# BLE_Monitor_Orientation_Sensor.net
KiCad netlist of a schematic drawn in EAGLE
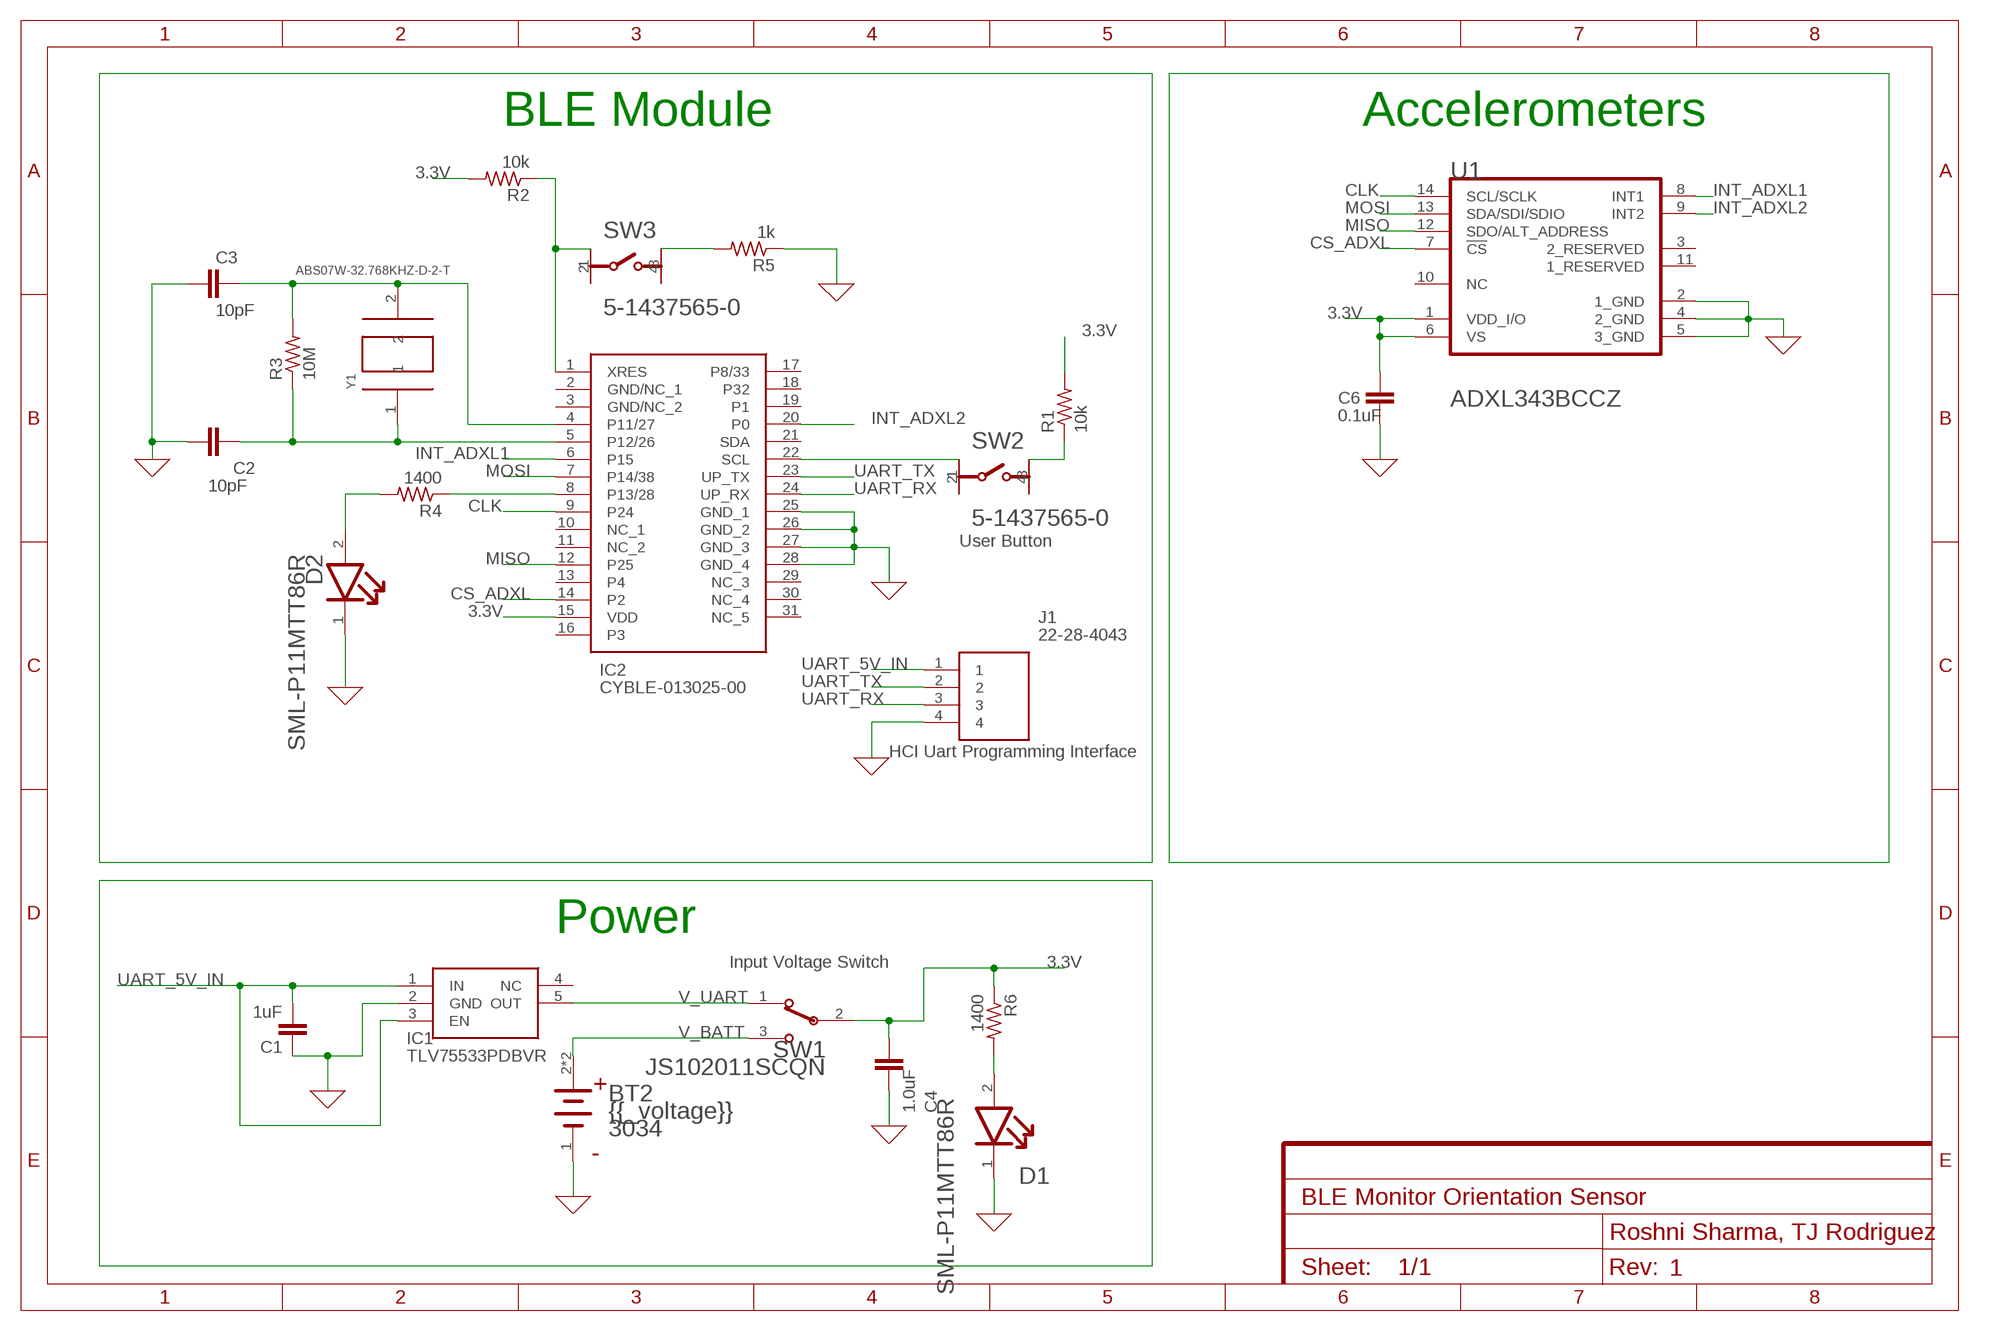
[diagram p0: schematic, sheet 1]

(export (version "E")
  (design (tool "Eeschema 10.0.6"))
  (components
    (comp (ref "BT2")
      (value "KEYSTONE_ELECTRONICS_3034KEYSTONE_ELECTRONICS_3034_0_0")
      (footprint "eagle-import:KEYSTONE_ELECTRONICS_3034_0")
      (fields
        (field (name "DIGIKEY_PART_NUMBER") "36-3034-ND")
        (field (name "MF") "Keystone Electronics")
        (field (name "MOUSER_PART_NUMBER") "534-3034")
      )
      (libsource (lib "eagle-import") (part "KEYSTONE_ELECTRONICS_3034KEYSTONE_ELECTRONICS_3034_0_0"))
    )
    (comp (ref "C1")
      (value "1uF")
      (footprint "eagle-import:0603")
      (libsource (lib "eagle-import") (part "10PF-0603-50V-5%"))
    )
    (comp (ref "C2")
      (value "10pF")
      (footprint "eagle-import:0603")
      (libsource (lib "eagle-import") (part "10PF-0603-50V-5%"))
    )
    (comp (ref "C3")
      (value "10pF")
      (footprint "eagle-import:0603")
      (libsource (lib "eagle-import") (part "10PF-0603-50V-5%"))
    )
    (comp (ref "C4")
      (value "1.0uF")
      (footprint "eagle-import:0603")
      (libsource (lib "eagle-import") (part "1.0UF-0603-16V-10%"))
    )
    (comp (ref "C6")
      (value "0.1uF")
      (footprint "eagle-import:0603")
      (libsource (lib "eagle-import") (part "10PF-0603-50V-5%"))
    )
    (comp (ref "D1")
      (value "ROHM_SML-P11MTT86RROHM_SML-P11MTT86R_0_0")
      (footprint "eagle-import:ROHM_SML-P11MTT86R_0")
      (fields
        (field (name "DIGIKEY_PART_NUMBER") "846-1211-1-ND")
        (field (name "MF") "ROHM")
        (field (name "MOUSER_PART_NUMBER") "755-SML-P11MTT86R")
      )
      (libsource (lib "eagle-import") (part "ROHM_SML-P11MTT86RROHM_SML-P11MTT86R_0_0"))
    )
    (comp (ref "D2")
      (value "ROHM_SML-P11MTT86RROHM_SML-P11MTT86R_0_0")
      (footprint "eagle-import:ROHM_SML-P11MTT86R_0")
      (fields
        (field (name "DIGIKEY_PART_NUMBER") "846-1211-1-ND")
        (field (name "MF") "ROHM")
        (field (name "MOUSER_PART_NUMBER") "755-SML-P11MTT86R")
      )
      (libsource (lib "eagle-import") (part "ROHM_SML-P11MTT86RROHM_SML-P11MTT86R_0_0"))
    )
    (comp (ref "IC1")
      (value "TLV75533PDBVR")
      (footprint "eagle-import:SOT95P280X145-5N")
      (fields (field (name "MOUSER_PART_NUMBER") "595-TLV75533PDBVR"))
      (libsource (lib "eagle-import") (part "TLV75533PDBVR"))
    )
    (comp (ref "IC2")
      (value "CYBLE-013025-00")
      (footprint "eagle-import:CYBLE01302500")
      (fields (field (name "MOUSER_PART_NUMBER") "727-CYBLE-013025-00") (field (name "SPICEPREFIX") "X"))
      (libsource (lib "eagle-import") (part "CYBLE-013025-00"))
    )
    (comp (ref "J1")
      (value "22-28-4043")
      (footprint "eagle-import:HDRV4W87P0X254_1X4_1016X249X86")
      (fields
        (field (name "MOUSER_PART_NUMBER") "538-22-28-4043")
        (field (name "FUNCTION") "HCI Uart Programming Interface")
      )
      (libsource (lib "eagle-import") (part "22-28-4043"))
    )
    (comp (ref "R1")
      (value "10k")
      (footprint "eagle-import:R0603")
      (libsource (lib "eagle-import") (part "R-US_R0603"))
    )
    (comp (ref "R2")
      (value "10k")
      (footprint "eagle-import:R0603")
      (libsource (lib "eagle-import") (part "R-US_R0603"))
    )
    (comp (ref "R3")
      (value "10M")
      (footprint "eagle-import:R0603")
      (libsource (lib "eagle-import") (part "R-US_R0603"))
    )
    (comp (ref "R4")
      (value "1400")
      (footprint "eagle-import:R0603")
      (libsource (lib "eagle-import") (part "R-US_R0603"))
    )
    (comp (ref "R5")
      (value "1k")
      (footprint "eagle-import:R0603")
      (libsource (lib "eagle-import") (part "R-US_R0603"))
    )
    (comp (ref "R6")
      (value "1400")
      (footprint "eagle-import:R0603")
      (libsource (lib "eagle-import") (part "R-US_R0603"))
    )
    (comp (ref "SW1")
      (value "C&K_JS102011SCQNC&K_JS102011SCQN_0_0")
      (footprint "eagle-import:C&K_JS102011SCQN_0")
      (fields
        (field (name "DIGIKEY_PART_NUMBER") "CKN10877CT-ND")
        (field (name "MF") "C&K")
        (field (name "MOUSER_PART_NUMBER") "611-JS102011SCQN")
        (field (name "FUNCTION") "Input Voltage Switch")
      )
      (libsource (lib "eagle-import") (part "C&K_JS102011SCQNC&K_JS102011SCQN_0_0"))
    )
    (comp (ref "SW2")
      (value "TE_CONNECTIVITY_5-1437565-0TE_CONNECTIVITY_5-1437565-0_0_0")
      (footprint "eagle-import:TE_CONNECTIVITY_5-1437565-0_0")
      (fields
        (field (name "DIGIKEY_PART_NUMBER") "450-2058-1-ND")
        (field (name "MF") "TE Connectivity")
        (field (name "MOUSER_PART_NUMBER") "506-5-1437565-0")
        (field (name "FUNCTION") "User Button")
      )
      (libsource (lib "eagle-import") (part "TE_CONNECTIVITY_5-1437565-0TE_CONNECTIVITY_5-1437565-0_0_0"))
    )
    (comp (ref "SW3")
      (value "TE_CONNECTIVITY_5-1437565-0TE_CONNECTIVITY_5-1437565-0_0_0")
      (footprint "eagle-import:TE_CONNECTIVITY_5-1437565-0_0")
      (fields
        (field (name "DIGIKEY_PART_NUMBER") "450-2058-1-ND")
        (field (name "MF") "TE Connectivity")
        (field (name "MOUSER_PART_NUMBER") "506-5-1437565-0")
      )
      (libsource (lib "eagle-import") (part "TE_CONNECTIVITY_5-1437565-0TE_CONNECTIVITY_5-1437565-0_0_0"))
    )
    (comp (ref "U1")
      (value "ANALOG_DEVICES_ADXL343BCCZANALOG_DEVICES_ADXL343BCCZ_0_0")
      (footprint "eagle-import:ANALOG_DEVICES_ADXL343BCCZ_0")
      (fields (field (name "MF") "Analog Devices") (field (name "MPN") "ADXL343BCCZ"))
      (libsource (lib "eagle-import") (part "ANALOG_DEVICES_ADXL343BCCZANALOG_DEVICES_ADXL343BCCZ_0_0"))
    )
    (comp (ref "Y1")
      (value "ABS07W-32.768KHZ-D-2-T")
      (footprint "eagle-import:XTAL320X150X90")
      (fields
        (field (name "DIGI-KEY_PART_NUMBER") "535-14105-1-ND")
        (field (name "MF") "Abracon")
        (field (name "SPICEPREFIX") "B")
      )
      (libsource (lib "eagle-import") (part "ABS07W-32.768KHZ-D-2-T"))
    )
  )
  (nets
    (net (code "1") (name "/3.3V") (class "Default")
      (node (ref "C4") (pin "1") (pinfunction "1_1") (pintype "passive"))
      (node (ref "C6") (pin "2") (pinfunction "2_2") (pintype "passive"))
      (node (ref "IC2") (pin "15") (pinfunction "VDD_15") (pintype "bidirectional"))
      (node (ref "R1") (pin "2") (pinfunction "2_2") (pintype "passive"))
      (node (ref "R2") (pin "2") (pinfunction "2_2") (pintype "passive"))
      (node (ref "R6") (pin "1") (pinfunction "1_1") (pintype "passive"))
      (node (ref "SW1") (pin "2") (pinfunction "2_2") (pintype "passive"))
      (node (ref "U1") (pin "1") (pinfunction "VDD_I/O_1") (pintype "power_in"))
      (node (ref "U1") (pin "6") (pinfunction "VS_6") (pintype "power_in"))
    )
    (net (code "2") (name "/CLK") (class "Default")
      (node (ref "IC2") (pin "9") (pinfunction "P24_9") (pintype "bidirectional"))
      (node (ref "U1") (pin "14") (pinfunction "SCL/SCLK_14") (pintype "input"))
    )
    (net (code "3") (name "/CS_ADXL") (class "Default")
      (node (ref "IC2") (pin "14") (pinfunction "P2_14") (pintype "bidirectional"))
      (node (ref "U1") (pin "7") (pinfunction "~{CS}_7") (pintype "input"))
    )
    (net (code "4") (name "/INT_ADXL1") (class "Default")
      (node (ref "IC2") (pin "6") (pinfunction "P15_6") (pintype "bidirectional"))
      (node (ref "U1") (pin "8") (pinfunction "INT1_8") (pintype "output"))
    )
    (net (code "5") (name "/INT_ADXL2") (class "Default")
      (node (ref "IC2") (pin "20") (pinfunction "P0_20") (pintype "bidirectional"))
      (node (ref "U1") (pin "9") (pinfunction "INT2_9") (pintype "output"))
    )
    (net (code "6") (name "/MISO") (class "Default")
      (node (ref "IC2") (pin "12") (pinfunction "P25_12") (pintype "bidirectional"))
      (node (ref "U1") (pin "12") (pinfunction "SDO/ALT_ADDRESS_12") (pintype "bidirectional"))
    )
    (net (code "7") (name "/MOSI") (class "Default")
      (node (ref "IC2") (pin "7") (pinfunction "P14/38_7") (pintype "bidirectional"))
      (node (ref "U1") (pin "13") (pinfunction "SDA/SDI/SDIO_13") (pintype "bidirectional"))
    )
    (net (code "8") (name "/UART_5V_IN") (class "Default")
      (node (ref "C1") (pin "2") (pinfunction "2_2") (pintype "passive"))
      (node (ref "IC1") (pin "1") (pinfunction "IN_1") (pintype "bidirectional"))
      (node (ref "IC1") (pin "3") (pinfunction "EN_3") (pintype "bidirectional"))
      (node (ref "J1") (pin "1") (pinfunction "1_1") (pintype "bidirectional"))
    )
    (net (code "9") (name "/UART_RX") (class "Default")
      (node (ref "IC2") (pin "24") (pinfunction "UP_RX_24") (pintype "bidirectional"))
      (node (ref "J1") (pin "3") (pinfunction "3_3") (pintype "bidirectional"))
    )
    (net (code "10") (name "/UART_TX") (class "Default")
      (node (ref "IC2") (pin "23") (pinfunction "UP_TX_23") (pintype "bidirectional"))
      (node (ref "J1") (pin "2") (pinfunction "2_2") (pintype "bidirectional"))
    )
    (net (code "11") (name "/V_BATT") (class "Default")
      (node (ref "BT2") (pin "2") (pinfunction "ANODE_2") (pintype "passive"))
      (node (ref "BT2") (pin "2-2") (pinfunction "ANODE_2-2") (pintype "passive"))
      (node (ref "SW1") (pin "3") (pinfunction "3_3") (pintype "passive"))
    )
    (net (code "12") (name "/V_UART") (class "Default")
      (node (ref "IC1") (pin "5") (pinfunction "OUT_5") (pintype "bidirectional"))
      (node (ref "SW1") (pin "1") (pinfunction "1_1") (pintype "passive"))
    )
    (net (code "13") (name "GND") (class "Default")
      (node (ref "BT2") (pin "1") (pinfunction "CATHODE_1") (pintype "passive"))
      (node (ref "C1") (pin "1") (pinfunction "1_1") (pintype "passive"))
      (node (ref "C2") (pin "1") (pinfunction "1_1") (pintype "passive"))
      (node (ref "C3") (pin "1") (pinfunction "1_1") (pintype "passive"))
      (node (ref "C4") (pin "2") (pinfunction "2_2") (pintype "passive"))
      (node (ref "C6") (pin "1") (pinfunction "1_1") (pintype "passive"))
      (node (ref "D1") (pin "1") (pinfunction "CATHODE_1") (pintype "passive"))
      (node (ref "D2") (pin "1") (pinfunction "CATHODE_1") (pintype "passive"))
      (node (ref "IC1") (pin "2") (pinfunction "GND_2") (pintype "bidirectional"))
      (node (ref "IC2") (pin "25") (pinfunction "GND_1_25") (pintype "bidirectional"))
      (node (ref "IC2") (pin "26") (pinfunction "GND_2_26") (pintype "bidirectional"))
      (node (ref "IC2") (pin "27") (pinfunction "GND_3_27") (pintype "bidirectional"))
      (node (ref "IC2") (pin "28") (pinfunction "GND_4_28") (pintype "bidirectional"))
      (node (ref "J1") (pin "4") (pinfunction "4_4") (pintype "bidirectional"))
      (node (ref "R5") (pin "1") (pinfunction "1_1") (pintype "passive"))
      (node (ref "U1") (pin "2") (pinfunction "1_GND_2") (pintype "power_in"))
      (node (ref "U1") (pin "4") (pinfunction "2_GND_4") (pintype "power_in"))
      (node (ref "U1") (pin "5") (pinfunction "3_GND_5") (pintype "power_in"))
    )
    (net (code "14") (name "Net-(D1-ANODE)") (class "Default")
      (node (ref "D1") (pin "2") (pinfunction "ANODE_2") (pintype "passive"))
      (node (ref "R6") (pin "2") (pinfunction "2_2") (pintype "passive"))
    )
    (net (code "15") (name "Net-(D2-ANODE)") (class "Default")
      (node (ref "D2") (pin "2") (pinfunction "ANODE_2") (pintype "passive"))
      (node (ref "R4") (pin "2") (pinfunction "2_2") (pintype "passive"))
    )
    (net (code "16") (name "Net-(IC2-P11{slash}27)") (class "Default")
      (node (ref "C3") (pin "2") (pinfunction "2_2") (pintype "passive"))
      (node (ref "IC2") (pin "4") (pinfunction "P11/27_4") (pintype "bidirectional"))
      (node (ref "R3") (pin "2") (pinfunction "2_2") (pintype "passive"))
      (node (ref "Y1") (pin "2") (pinfunction "2_2") (pintype "passive"))
    )
    (net (code "17") (name "Net-(IC2-P12{slash}26)") (class "Default")
      (node (ref "C2") (pin "2") (pinfunction "2_2") (pintype "passive"))
      (node (ref "IC2") (pin "5") (pinfunction "P12/26_5") (pintype "bidirectional"))
      (node (ref "R3") (pin "1") (pinfunction "1_1") (pintype "passive"))
      (node (ref "Y1") (pin "1") (pinfunction "1_1") (pintype "passive"))
    )
    (net (code "18") (name "Net-(IC2-P13{slash}28)") (class "Default")
      (node (ref "IC2") (pin "8") (pinfunction "P13/28_8") (pintype "bidirectional"))
      (node (ref "R4") (pin "1") (pinfunction "1_1") (pintype "passive"))
    )
    (net (code "19") (name "Net-(IC2-SCL)") (class "Default")
      (node (ref "IC2") (pin "22") (pinfunction "SCL_22") (pintype "bidirectional"))
      (node (ref "SW2") (pin "1") (pinfunction "1_1") (pintype "passive"))
    )
    (net (code "20") (name "Net-(IC2-XRES)") (class "Default")
      (node (ref "IC2") (pin "1") (pinfunction "XRES_1") (pintype "bidirectional"))
      (node (ref "R2") (pin "1") (pinfunction "1_1") (pintype "passive"))
      (node (ref "SW3") (pin "1") (pinfunction "1_1") (pintype "passive"))
    )
    (net (code "21") (name "Net-(R1-Pad1)") (class "Default")
      (node (ref "R1") (pin "1") (pinfunction "1_1") (pintype "passive"))
      (node (ref "SW2") (pin "3") (pinfunction "3_3") (pintype "passive"))
    )
    (net (code "22") (name "Net-(R5-Pad2)") (class "Default")
      (node (ref "R5") (pin "2") (pinfunction "2_2") (pintype "passive"))
      (node (ref "SW3") (pin "3") (pinfunction "3_3") (pintype "passive"))
    )
    (net (code "23") (name "unconnected-(IC1-NC-Pad4)") (class "Default")
      (node (ref "IC1") (pin "4") (pinfunction "NC_4") (pintype "no_connect"))
    )
    (net (code "24") (name "unconnected-(IC2-GND{slash}NC_1-Pad2)") (class "Default")
      (node (ref "IC2") (pin "2") (pinfunction "GND/NC_1_2") (pintype "bidirectional"))
    )
    (net (code "25") (name "unconnected-(IC2-GND{slash}NC_2-Pad3)") (class "Default")
      (node (ref "IC2") (pin "3") (pinfunction "GND/NC_2_3") (pintype "bidirectional"))
    )
    (net (code "26") (name "unconnected-(IC2-NC_1-Pad10)") (class "Default")
      (node (ref "IC2") (pin "10") (pinfunction "NC_1_10") (pintype "bidirectional"))
    )
    (net (code "27") (name "unconnected-(IC2-NC_2-Pad11)") (class "Default")
      (node (ref "IC2") (pin "11") (pinfunction "NC_2_11") (pintype "bidirectional"))
    )
    (net (code "28") (name "unconnected-(IC2-NC_3-Pad29)") (class "Default")
      (node (ref "IC2") (pin "29") (pinfunction "NC_3_29") (pintype "bidirectional"))
    )
    (net (code "29") (name "unconnected-(IC2-NC_4-Pad30)") (class "Default")
      (node (ref "IC2") (pin "30") (pinfunction "NC_4_30") (pintype "bidirectional"))
    )
    (net (code "30") (name "unconnected-(IC2-NC_5-Pad31)") (class "Default")
      (node (ref "IC2") (pin "31") (pinfunction "NC_5_31") (pintype "bidirectional"))
    )
    (net (code "31") (name "unconnected-(IC2-P1-Pad19)") (class "Default")
      (node (ref "IC2") (pin "19") (pinfunction "P1_19") (pintype "bidirectional"))
    )
    (net (code "32") (name "unconnected-(IC2-P3-Pad16)") (class "Default")
      (node (ref "IC2") (pin "16") (pinfunction "P3_16") (pintype "bidirectional"))
    )
    (net (code "33") (name "unconnected-(IC2-P4-Pad13)") (class "Default")
      (node (ref "IC2") (pin "13") (pinfunction "P4_13") (pintype "bidirectional"))
    )
    (net (code "34") (name "unconnected-(IC2-P8{slash}33-Pad17)") (class "Default")
      (node (ref "IC2") (pin "17") (pinfunction "P8/33_17") (pintype "bidirectional"))
    )
    (net (code "35") (name "unconnected-(IC2-P32-Pad18)") (class "Default")
      (node (ref "IC2") (pin "18") (pinfunction "P32_18") (pintype "bidirectional"))
    )
    (net (code "36") (name "unconnected-(IC2-SDA-Pad21)") (class "Default")
      (node (ref "IC2") (pin "21") (pinfunction "SDA_21") (pintype "bidirectional"))
    )
    (net (code "37") (name "unconnected-(SW2-Pad2)") (class "Default")
      (node (ref "SW2") (pin "2") (pinfunction "2_2") (pintype "passive"))
    )
    (net (code "38") (name "unconnected-(SW2-Pad4)") (class "Default")
      (node (ref "SW2") (pin "4") (pinfunction "4_4") (pintype "passive"))
    )
    (net (code "39") (name "unconnected-(SW3-Pad2)") (class "Default")
      (node (ref "SW3") (pin "2") (pinfunction "2_2") (pintype "passive"))
    )
    (net (code "40") (name "unconnected-(SW3-Pad4)") (class "Default")
      (node (ref "SW3") (pin "4") (pinfunction "4_4") (pintype "passive"))
    )
    (net (code "41") (name "unconnected-(U1-1_RESERVED-Pad11)") (class "Default")
      (node (ref "U1") (pin "11") (pinfunction "1_RESERVED_11") (pintype "passive"))
    )
    (net (code "42") (name "unconnected-(U1-2_RESERVED-Pad3)") (class "Default")
      (node (ref "U1") (pin "3") (pinfunction "2_RESERVED_3") (pintype "passive"))
    )
    (net (code "43") (name "unconnected-(U1-NC-Pad10)") (class "Default")
      (node (ref "U1") (pin "10") (pinfunction "NC_10") (pintype "passive"))
    )
  )
)
